# mini-v1_6-spacing.net
KiCad netlist of a schematic drawn in EAGLE
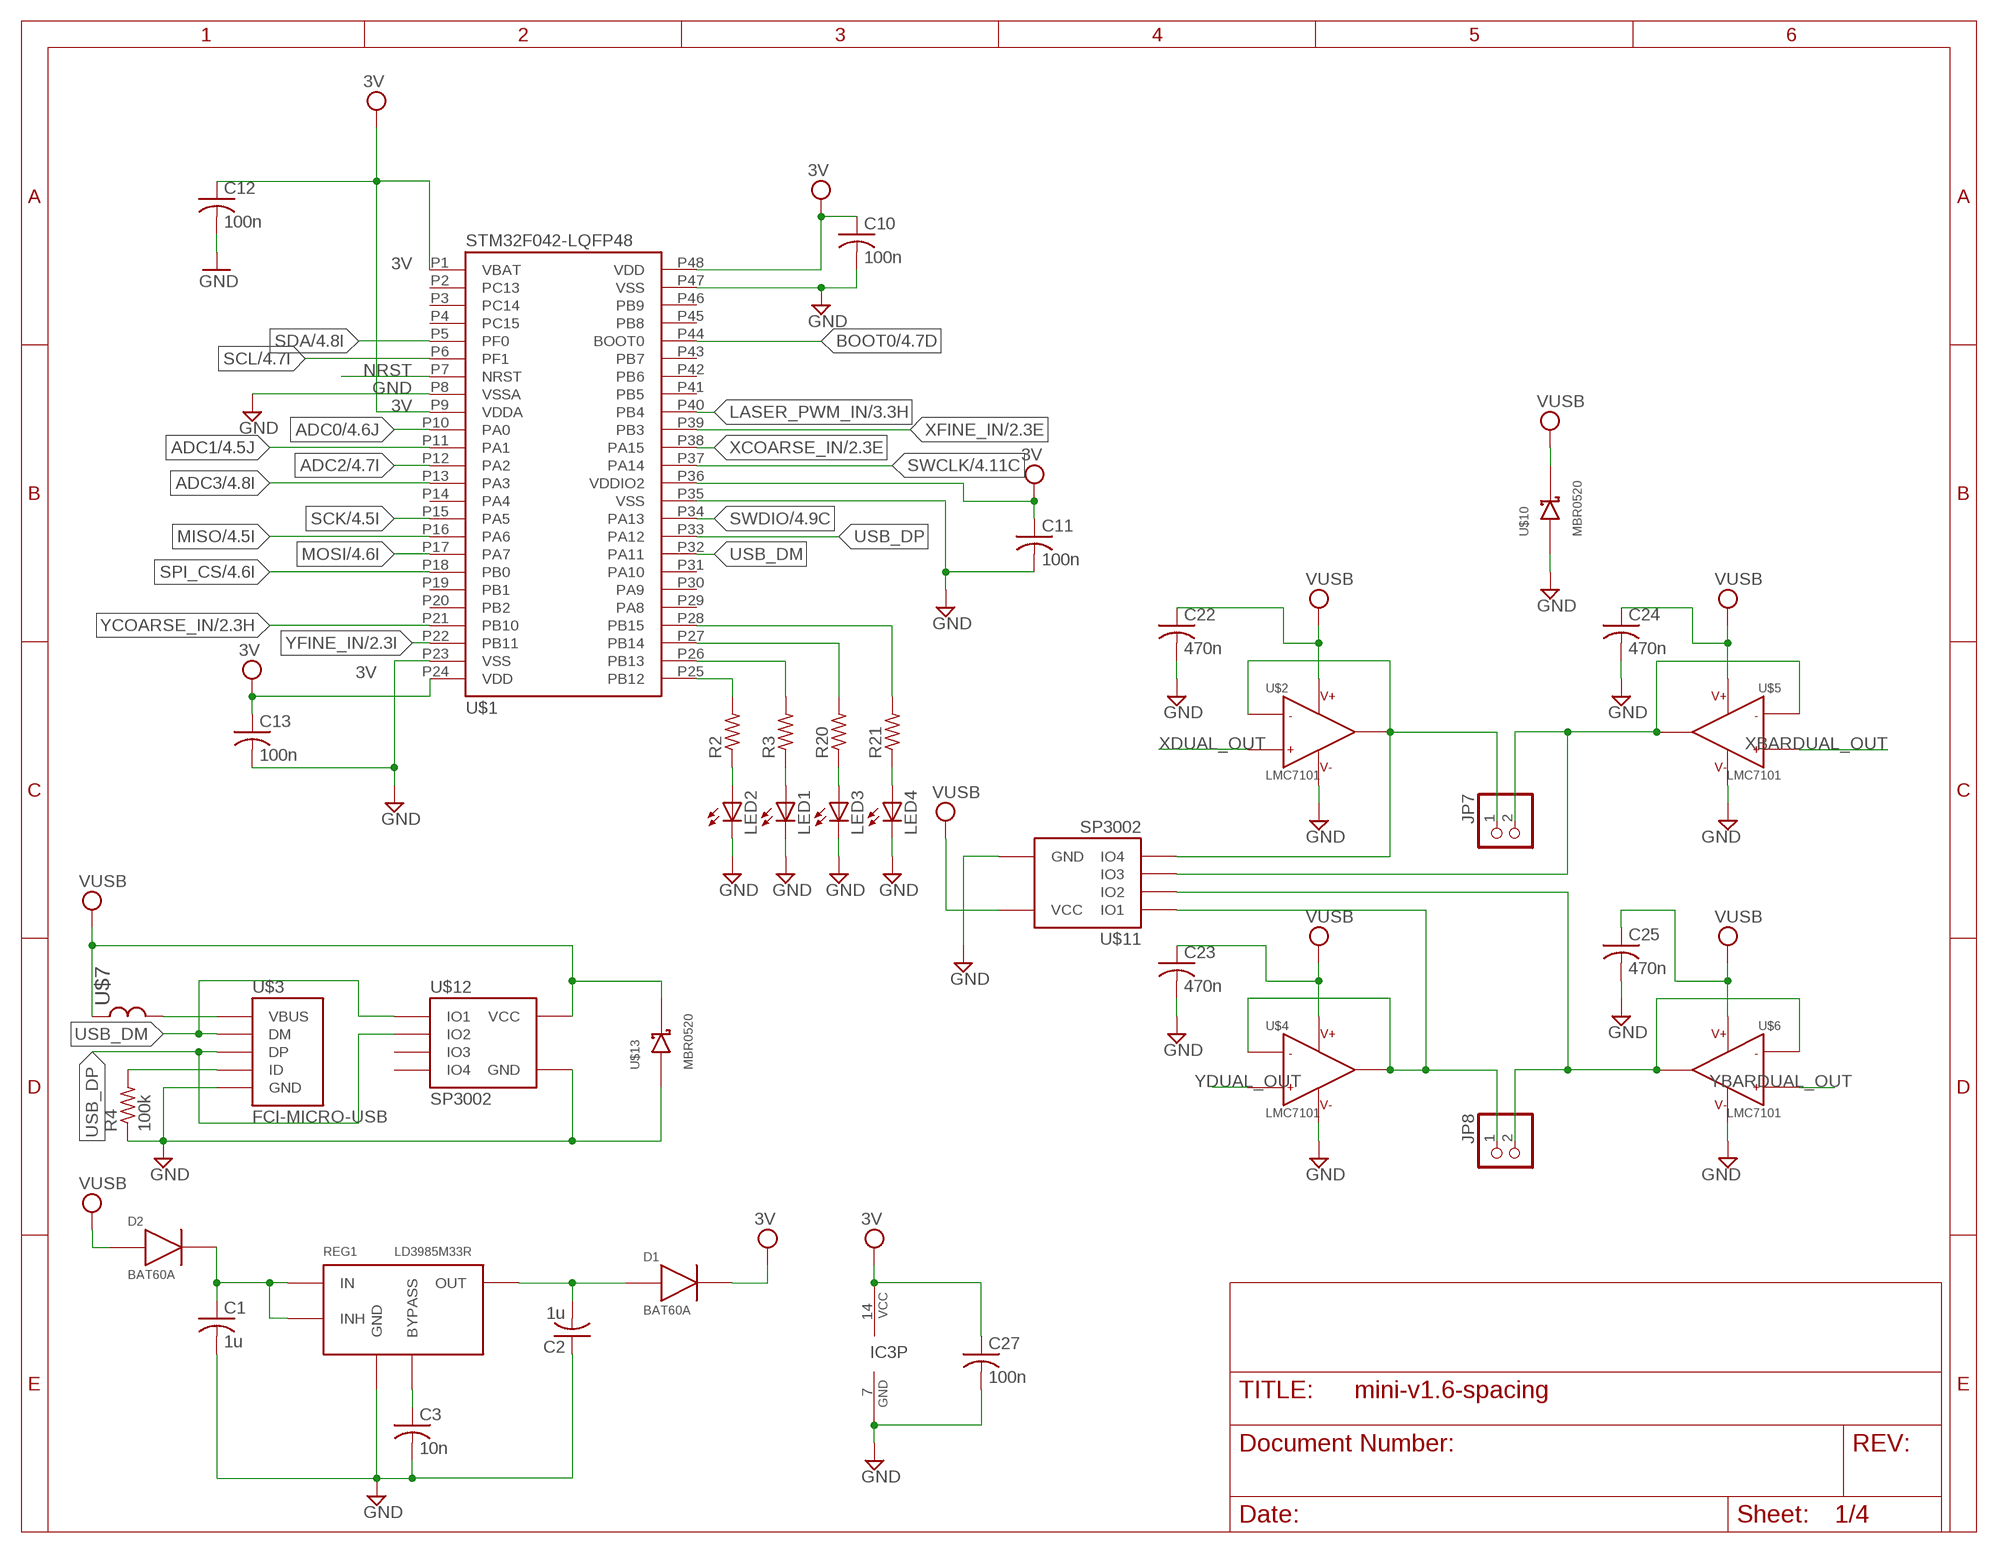
[diagram p0: schematic, sheet 1]
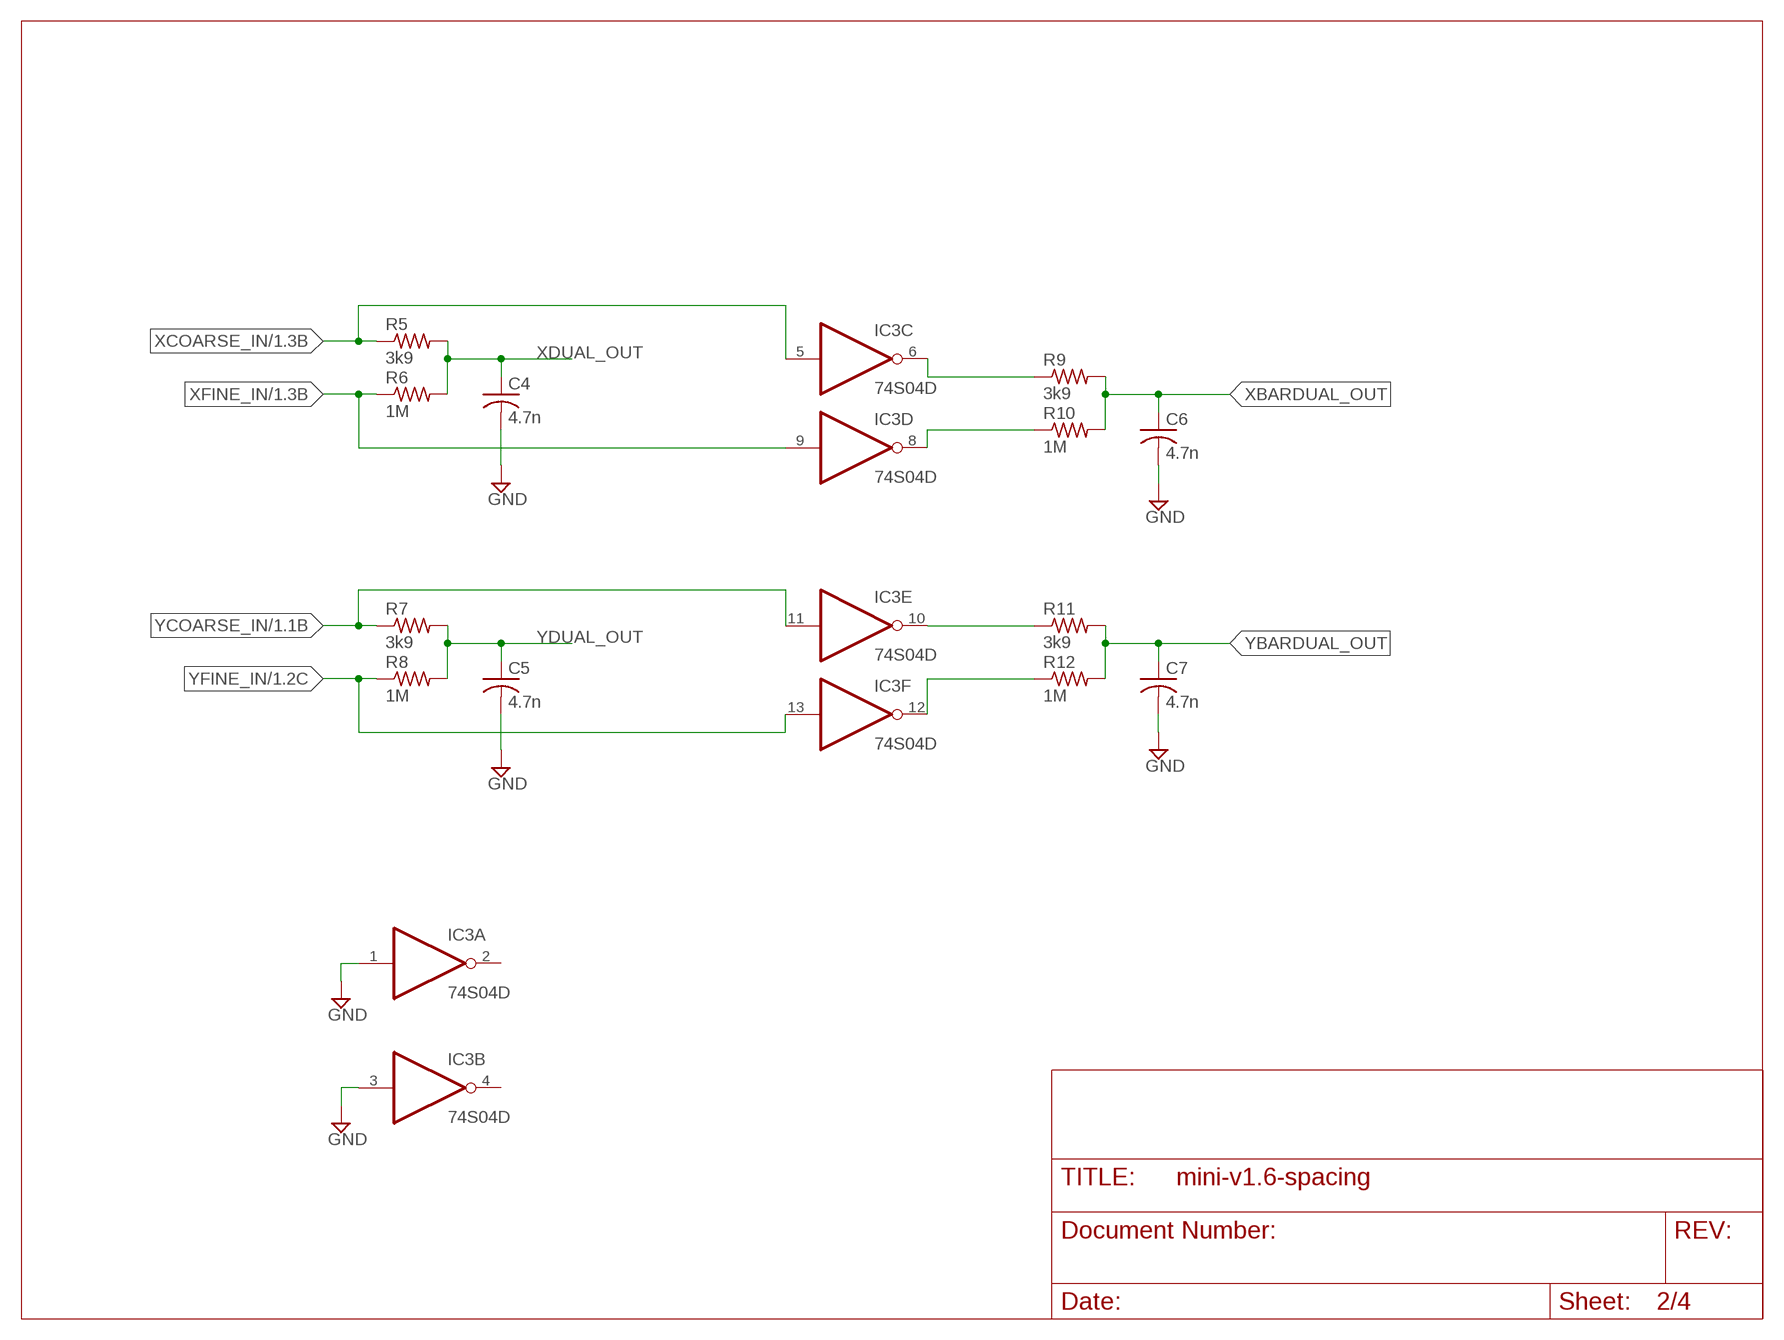
[diagram p1: schematic, sheet 2]
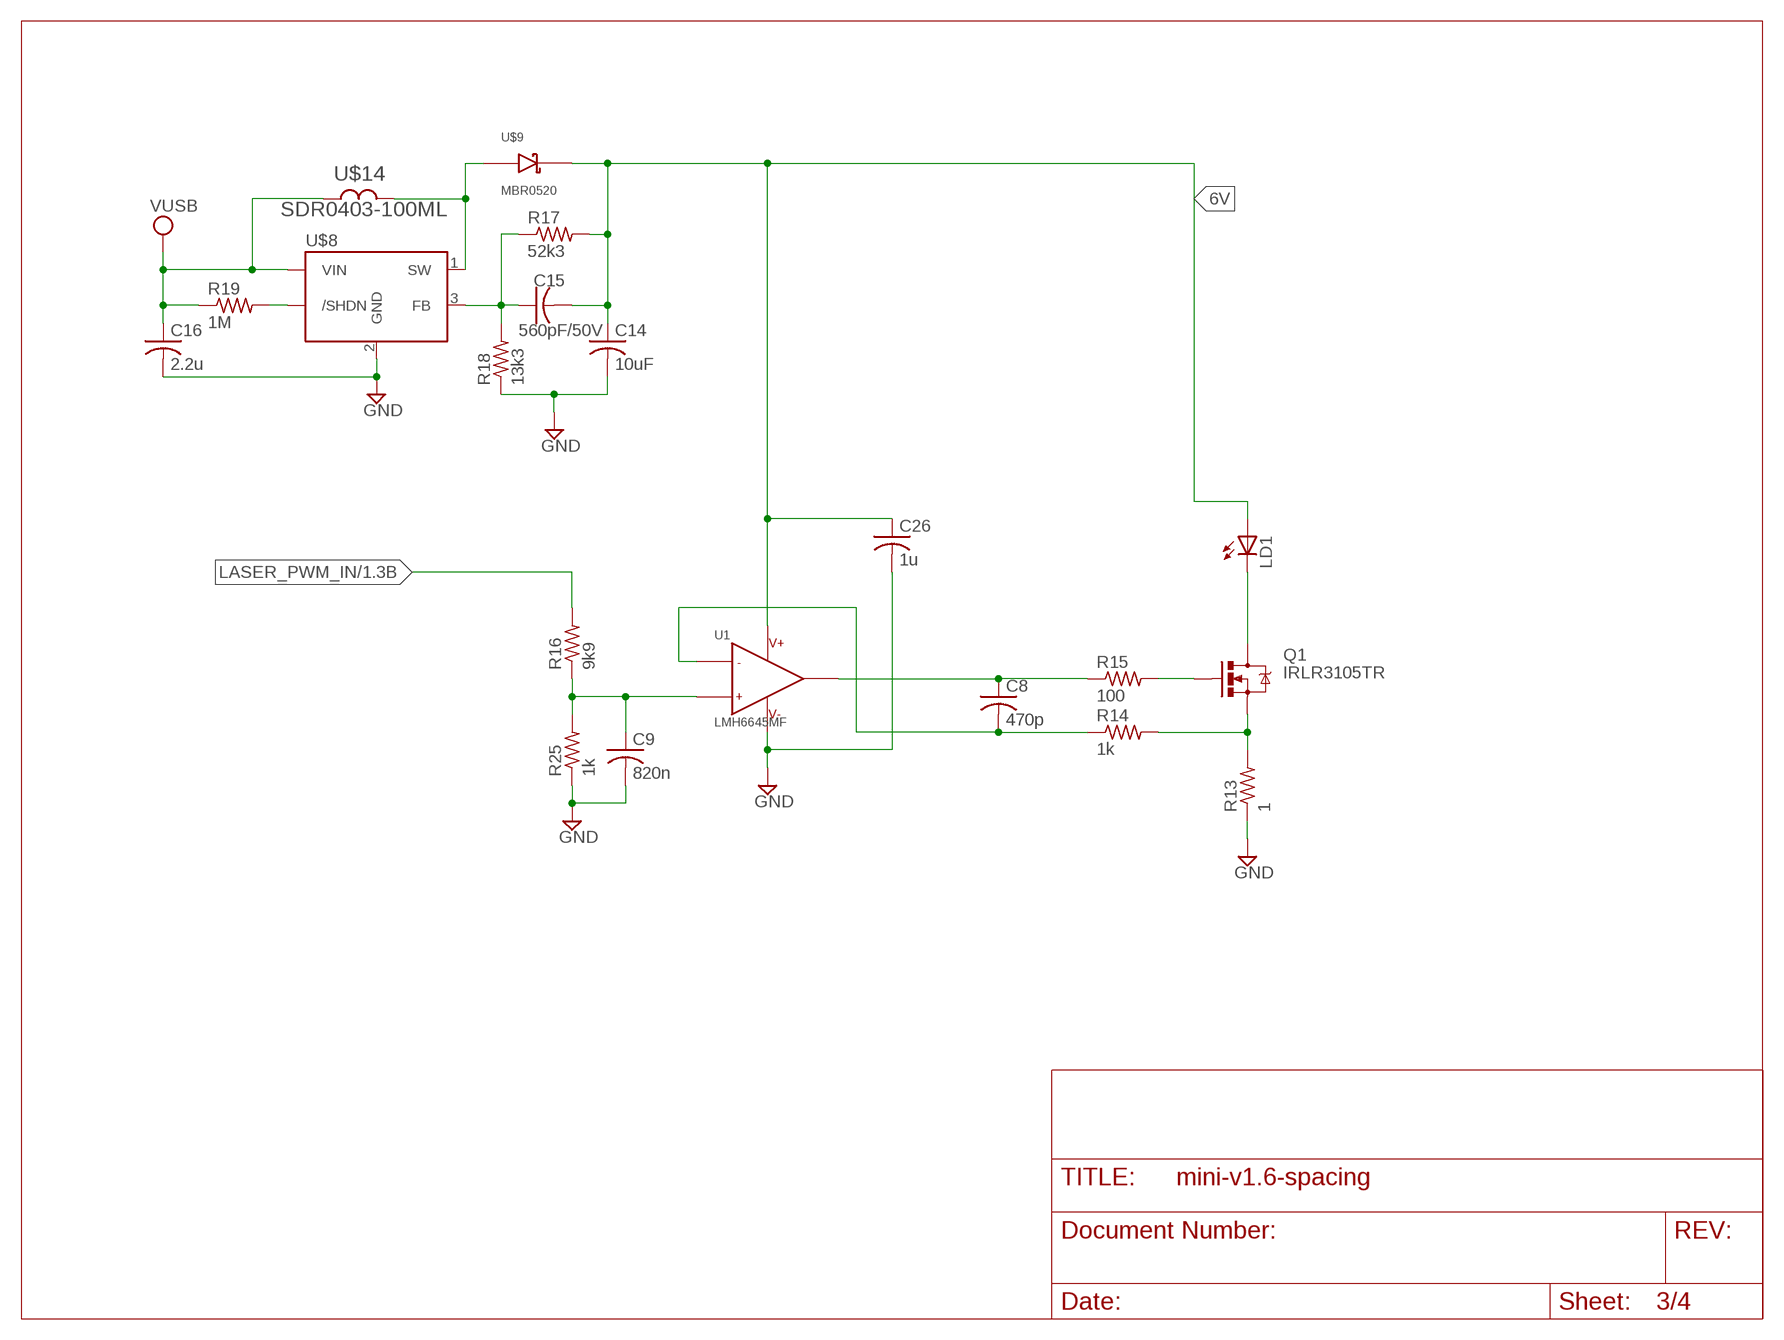
[diagram p2: schematic, sheet 3]
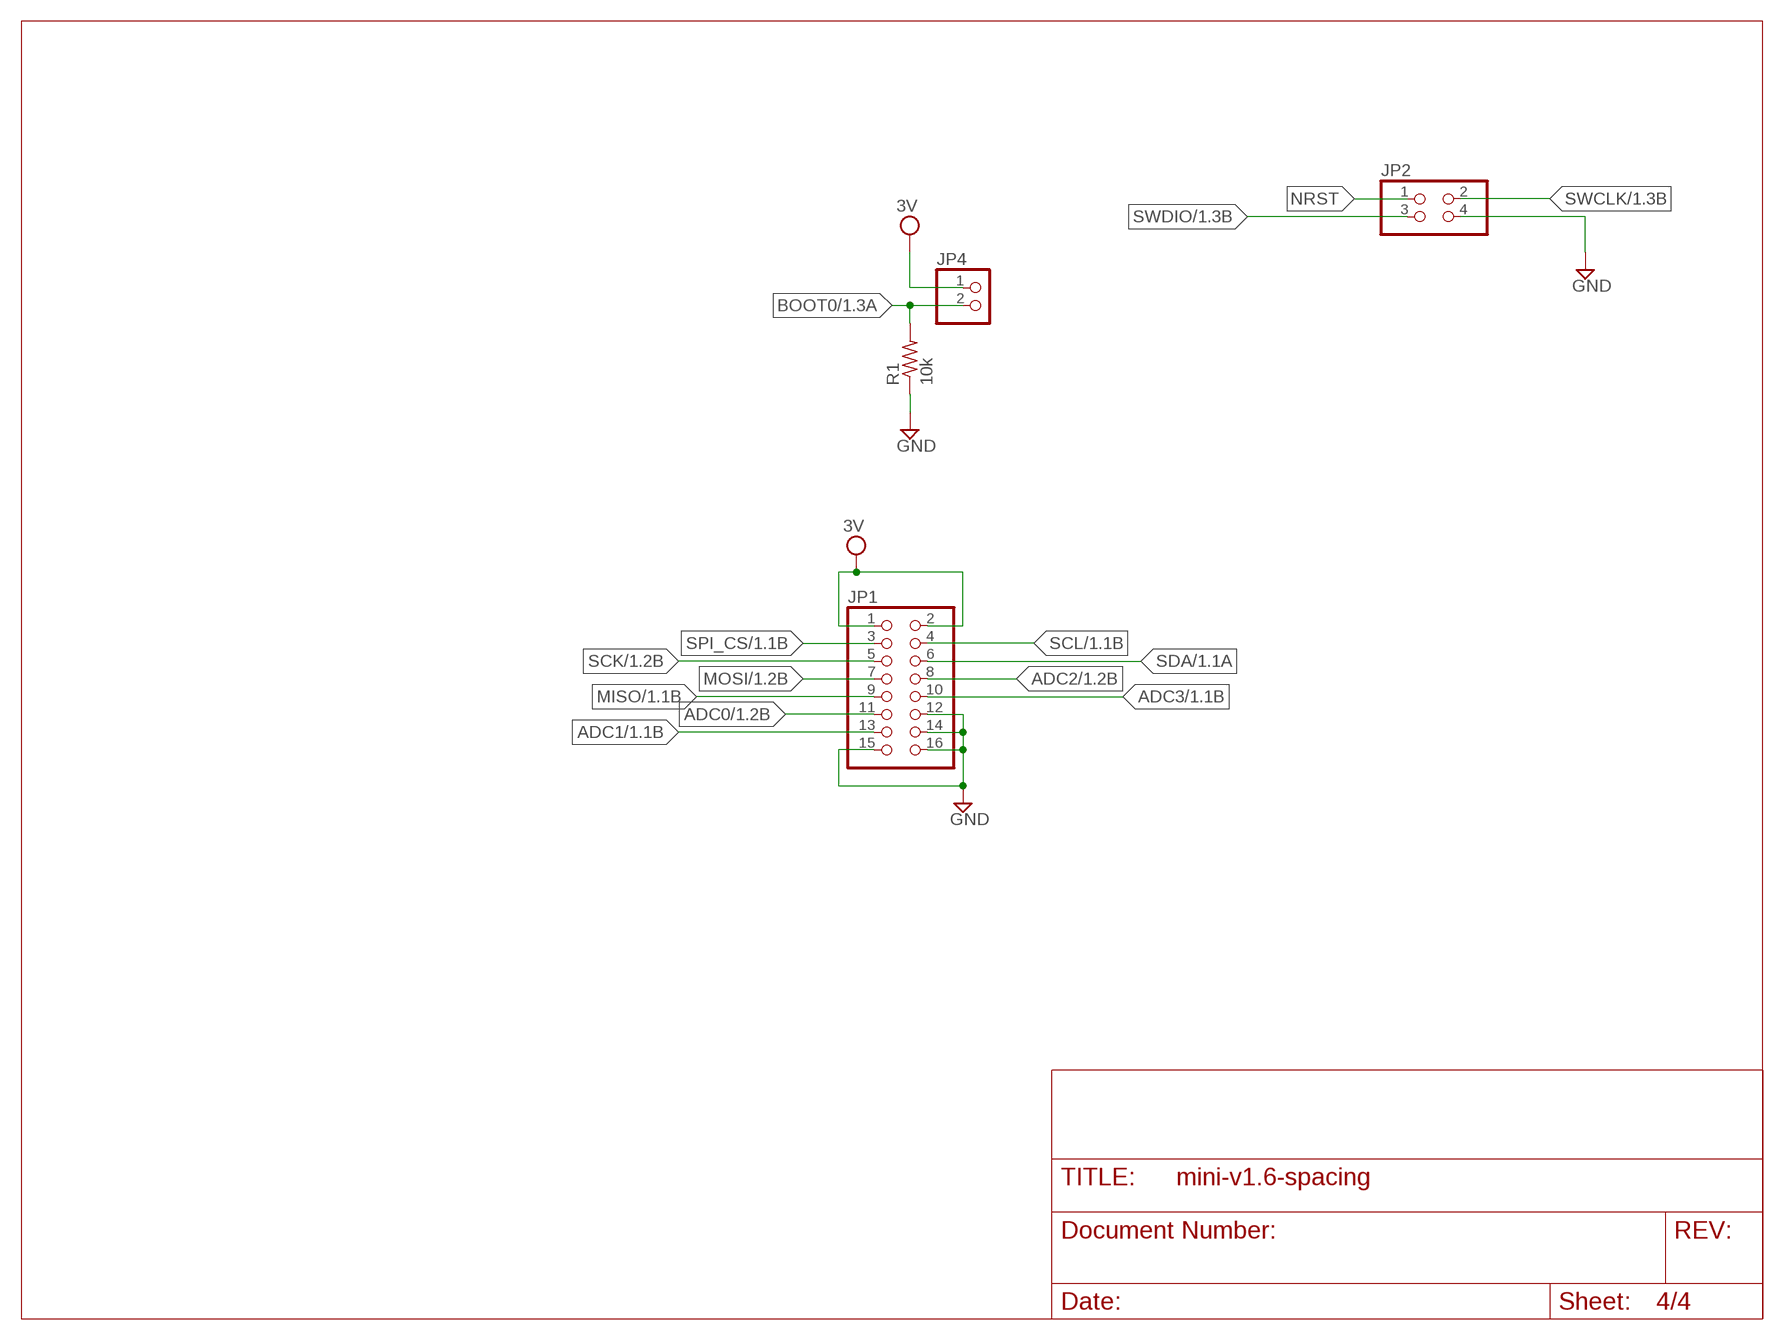
[diagram p3: schematic, sheet 4]

(export (version "E")
  (design (tool "Eeschema 10.0.6"))
  (components
    (comp (ref "C1")
      (value "1u")
      (footprint "eagle-import:C0603")
      (libsource (lib "eagle-import") (part "C-USC0603"))
    )
    (comp (ref "C2")
      (value "1u")
      (footprint "eagle-import:C0603")
      (libsource (lib "eagle-import") (part "C-USC0603"))
    )
    (comp (ref "C3")
      (value "10n")
      (footprint "eagle-import:C0603")
      (libsource (lib "eagle-import") (part "C-USC0603"))
    )
    (comp (ref "C10")
      (value "100n")
      (footprint "eagle-import:C0603")
      (libsource (lib "eagle-import") (part "C-USC0603"))
    )
    (comp (ref "C11")
      (value "100n")
      (footprint "eagle-import:C0603")
      (libsource (lib "eagle-import") (part "C-USC0603"))
    )
    (comp (ref "C12")
      (value "100n")
      (footprint "eagle-import:C0603")
      (libsource (lib "eagle-import") (part "C-USC0603"))
    )
    (comp (ref "C13")
      (value "100n")
      (footprint "eagle-import:C0603")
      (libsource (lib "eagle-import") (part "C-USC0603"))
    )
    (comp (ref "C22")
      (value "470n")
      (footprint "eagle-import:C0603")
      (libsource (lib "eagle-import") (part "C-USC0603"))
    )
    (comp (ref "C23")
      (value "470n")
      (footprint "eagle-import:C0603")
      (libsource (lib "eagle-import") (part "C-USC0603"))
    )
    (comp (ref "C24")
      (value "470n")
      (footprint "eagle-import:C0603")
      (libsource (lib "eagle-import") (part "C-USC0603"))
    )
    (comp (ref "C25")
      (value "470n")
      (footprint "eagle-import:C0603")
      (libsource (lib "eagle-import") (part "C-USC0603"))
    )
    (comp (ref "C27")
      (value "100n")
      (footprint "eagle-import:C0603")
      (libsource (lib "eagle-import") (part "C-USC0603"))
    )
    (comp (ref "D1")
      (value "BAT60A")
      (footprint "eagle-import:SOD323")
      (libsource (lib "eagle-import") (part "BAT60A"))
    )
    (comp (ref "D2")
      (value "BAT60A")
      (footprint "eagle-import:SOD323")
      (libsource (lib "eagle-import") (part "BAT60A"))
    )
    (comp (ref "IC3")
      (value "74S04D")
      (footprint "eagle-import:SO14")
      (libsource (lib "eagle-import") (part "7404DS"))
    )
    (comp (ref "JP7")
      (value "PINHD-1X2")
      (footprint "eagle-import:1X02")
      (libsource (lib "eagle-import") (part "PINHD-1X2"))
    )
    (comp (ref "JP8")
      (value "PINHD-1X2")
      (footprint "eagle-import:1X02")
      (libsource (lib "eagle-import") (part "PINHD-1X2"))
    )
    (comp (ref "LED1")
      (value "LEDCHIP-LED0603")
      (footprint "eagle-import:CHIP-LED0603")
      (libsource (lib "eagle-import") (part "LEDCHIP-LED0603"))
    )
    (comp (ref "LED2")
      (value "LEDCHIP-LED0603")
      (footprint "eagle-import:CHIP-LED0603")
      (libsource (lib "eagle-import") (part "LEDCHIP-LED0603"))
    )
    (comp (ref "LED3")
      (value "LEDCHIP-LED0603")
      (footprint "eagle-import:CHIP-LED0603")
      (libsource (lib "eagle-import") (part "LEDCHIP-LED0603"))
    )
    (comp (ref "LED4")
      (value "LEDCHIP-LED0603")
      (footprint "eagle-import:CHIP-LED0603")
      (libsource (lib "eagle-import") (part "LEDCHIP-LED0603"))
    )
    (comp (ref "R2")
      (value "R-US_R0603")
      (footprint "eagle-import:R0603")
      (libsource (lib "eagle-import") (part "R-US_R0603"))
    )
    (comp (ref "R3")
      (value "R-US_R0603")
      (footprint "eagle-import:R0603")
      (libsource (lib "eagle-import") (part "R-US_R0603"))
    )
    (comp (ref "R4")
      (value "100k")
      (footprint "eagle-import:R0603")
      (libsource (lib "eagle-import") (part "R-US_R0603"))
    )
    (comp (ref "R20")
      (value "R-US_R0603")
      (footprint "eagle-import:R0603")
      (libsource (lib "eagle-import") (part "R-US_R0603"))
    )
    (comp (ref "R21")
      (value "R-US_R0603")
      (footprint "eagle-import:R0603")
      (libsource (lib "eagle-import") (part "R-US_R0603"))
    )
    (comp (ref "REG1")
      (value "LD3985M33R")
      (footprint "eagle-import:SOT23-5L")
      (libsource (lib "eagle-import") (part "LD3985MXXR"))
    )
    (comp (ref "U$1")
      (value "STM32F042-LQFP48")
      (footprint "eagle-import:LQFP48")
      (libsource (lib "eagle-import") (part "STM32F042-LQFP48"))
    )
    (comp (ref "U$2")
      (value "LMC7101")
      (footprint "eagle-import:SOT23-5")
      (libsource (lib "eagle-import") (part "LMC7101"))
    )
    (comp (ref "U$3")
      (value "FCI-MICRO-USB")
      (footprint "eagle-import:FCI-MICROUSB")
      (libsource (lib "eagle-import") (part "FCI-MICRO-USB"))
    )
    (comp (ref "U$4")
      (value "LMC7101")
      (footprint "eagle-import:SOT23-5")
      (libsource (lib "eagle-import") (part "LMC7101"))
    )
    (comp (ref "U$5")
      (value "LMC7101")
      (footprint "eagle-import:SOT23-5")
      (libsource (lib "eagle-import") (part "LMC7101"))
    )
    (comp (ref "U$6")
      (value "LMC7101")
      (footprint "eagle-import:SOT23-5")
      (libsource (lib "eagle-import") (part "LMC7101"))
    )
    (comp (ref "U$7")
      (value "L_TDK_1005")
      (footprint "eagle-import:MLK1005")
      (libsource (lib "eagle-import") (part "L_TDK_1005"))
    )
    (comp (ref "U$10")
      (value "MBR0520")
      (footprint "eagle-import:SOD123")
      (libsource (lib "eagle-import") (part "MBR0520"))
    )
    (comp (ref "U$11")
      (value "SP3002")
      (footprint "eagle-import:SC70-6")
      (libsource (lib "eagle-import") (part "SP3002"))
    )
    (comp (ref "U$12")
      (value "SP3002")
      (footprint "eagle-import:SC70-6")
      (libsource (lib "eagle-import") (part "SP3002"))
    )
    (comp (ref "U$13")
      (value "MBR0520")
      (footprint "eagle-import:SOD123")
      (libsource (lib "eagle-import") (part "MBR0520"))
    )
    (comp (ref "C4")
      (value "4.7n")
      (footprint "eagle-import:C0603")
      (libsource (lib "eagle-import") (part "C-USC0603"))
    )
    (comp (ref "C5")
      (value "4.7n")
      (footprint "eagle-import:C0603")
      (libsource (lib "eagle-import") (part "C-USC0603"))
    )
    (comp (ref "C6")
      (value "4.7n")
      (footprint "eagle-import:C0603")
      (libsource (lib "eagle-import") (part "C-USC0603"))
    )
    (comp (ref "C7")
      (value "4.7n")
      (footprint "eagle-import:C0603")
      (libsource (lib "eagle-import") (part "C-USC0603"))
    )
    (comp (ref "R5")
      (value "3k9")
      (footprint "eagle-import:R0603")
      (libsource (lib "eagle-import") (part "R-US_R0603"))
    )
    (comp (ref "R6")
      (value "1M")
      (footprint "eagle-import:R0603")
      (libsource (lib "eagle-import") (part "R-US_R0603"))
    )
    (comp (ref "R7")
      (value "3k9")
      (footprint "eagle-import:R0603")
      (libsource (lib "eagle-import") (part "R-US_R0603"))
    )
    (comp (ref "R8")
      (value "1M")
      (footprint "eagle-import:R0603")
      (libsource (lib "eagle-import") (part "R-US_R0603"))
    )
    (comp (ref "R9")
      (value "3k9")
      (footprint "eagle-import:R0603")
      (libsource (lib "eagle-import") (part "R-US_R0603"))
    )
    (comp (ref "R10")
      (value "1M")
      (footprint "eagle-import:R0603")
      (libsource (lib "eagle-import") (part "R-US_R0603"))
    )
    (comp (ref "R11")
      (value "3k9")
      (footprint "eagle-import:R0603")
      (libsource (lib "eagle-import") (part "R-US_R0603"))
    )
    (comp (ref "R12")
      (value "1M")
      (footprint "eagle-import:R0603")
      (libsource (lib "eagle-import") (part "R-US_R0603"))
    )
    (comp (ref "C8")
      (value "470p")
      (footprint "eagle-import:C0603")
      (libsource (lib "eagle-import") (part "C-USC0603"))
    )
    (comp (ref "C9")
      (value "820n")
      (footprint "eagle-import:C0603")
      (libsource (lib "eagle-import") (part "C-USC0603"))
    )
    (comp (ref "C14")
      (value "10uF")
      (footprint "eagle-import:C0603")
      (libsource (lib "eagle-import") (part "C-USC0603"))
    )
    (comp (ref "C15")
      (value "560pF/50V")
      (footprint "eagle-import:C0603")
      (libsource (lib "eagle-import") (part "C-USC0603"))
    )
    (comp (ref "C16")
      (value "2.2u")
      (footprint "eagle-import:C0603")
      (libsource (lib "eagle-import") (part "C-USC0603"))
    )
    (comp (ref "C26")
      (value "1u")
      (footprint "eagle-import:C0603")
      (libsource (lib "eagle-import") (part "C-USC0603"))
    )
    (comp (ref "LD1")
      (value "LASERDIODELD2")
      (footprint "eagle-import:LASERDIODE2")
      (fields (field (name "MPN") "3 x (0552-2-15-15-11-27-10-0)"))
      (libsource (lib "eagle-import") (part "LASERDIODELD2"))
    )
    (comp (ref "Q1")
      (value "IRLR3105TR")
      (footprint "eagle-import:DPAK")
      (libsource (lib "eagle-import") (part "FET-N-IRLR3105TRIRLR3105TR"))
    )
    (comp (ref "R13")
      (value "1")
      (footprint "eagle-import:R0603")
      (libsource (lib "eagle-import") (part "R-US_R0603"))
    )
    (comp (ref "R14")
      (value "1k")
      (footprint "eagle-import:R0603")
      (libsource (lib "eagle-import") (part "R-US_R0603"))
    )
    (comp (ref "R15")
      (value "100")
      (footprint "eagle-import:R0603")
      (libsource (lib "eagle-import") (part "R-US_R0603"))
    )
    (comp (ref "R16")
      (value "9k9")
      (footprint "eagle-import:R0603")
      (libsource (lib "eagle-import") (part "R-US_R0603"))
    )
    (comp (ref "R17")
      (value "52k3")
      (footprint "eagle-import:R0603")
      (libsource (lib "eagle-import") (part "R-US_R0603"))
    )
    (comp (ref "R18")
      (value "13k3")
      (footprint "eagle-import:R0603")
      (libsource (lib "eagle-import") (part "R-US_R0603"))
    )
    (comp (ref "R19")
      (value "1M")
      (footprint "eagle-import:R0603")
      (libsource (lib "eagle-import") (part "R-US_R0603"))
    )
    (comp (ref "R25")
      (value "1k")
      (footprint "eagle-import:R0603")
      (libsource (lib "eagle-import") (part "R-US_R0603"))
    )
    (comp (ref "U$8")
      (value "LMR62014")
      (footprint "eagle-import:SOT23-5")
      (libsource (lib "eagle-import") (part "LMR62014"))
    )
    (comp (ref "U$9")
      (value "MBR0520")
      (footprint "eagle-import:SOD123")
      (libsource (lib "eagle-import") (part "MBR0520"))
    )
    (comp (ref "U$14")
      (value "SDR0403-100ML")
      (footprint "eagle-import:SDR0403")
      (libsource (lib "eagle-import") (part "SDR0403"))
    )
    (comp (ref "U1")
      (value "LMH6645MF")
      (footprint "eagle-import:SOT23-5")
      (libsource (lib "eagle-import") (part "OPAMP-SINGLELMH6645MF"))
    )
    (comp (ref "JP1")
      (value "PINHD-2X8")
      (footprint "eagle-import:2X08")
      (libsource (lib "eagle-import") (part "PINHD-2X8"))
    )
    (comp (ref "JP2")
      (value "PINHD-2X2")
      (footprint "eagle-import:2X02")
      (libsource (lib "eagle-import") (part "PINHD-2X2"))
    )
    (comp (ref "JP4")
      (value "PINHD-1X2")
      (footprint "eagle-import:1X02")
      (libsource (lib "eagle-import") (part "PINHD-1X2"))
    )
    (comp (ref "R1")
      (value "10k")
      (footprint "eagle-import:R0603")
      (libsource (lib "eagle-import") (part "R-US_R0603"))
    )
  )
  (nets
    (net (code "1") (name "3V") (class "Default")
      (node (ref "C10") (pin "1") (pinfunction "1_1") (pintype "passive"))
      (node (ref "C11") (pin "1") (pinfunction "1_1") (pintype "passive"))
      (node (ref "C12") (pin "1") (pinfunction "1_1") (pintype "passive"))
      (node (ref "C13") (pin "1") (pinfunction "1_1") (pintype "passive"))
      (node (ref "C27") (pin "1") (pinfunction "1_1") (pintype "passive"))
      (node (ref "D1") (pin "1") (pinfunction "1_1") (pintype "bidirectional"))
      (node (ref "IC3") (pin "14") (pinfunction "VCC_14") (pintype "power_in"))
      (node (ref "JP1") (pin "1") (pinfunction "1_1") (pintype "passive"))
      (node (ref "JP1") (pin "2") (pinfunction "2_2") (pintype "passive"))
      (node (ref "JP4") (pin "1") (pinfunction "1_1") (pintype "passive"))
      (node (ref "U$1") (pin "P1") (pinfunction "VBAT_P1") (pintype "bidirectional"))
      (node (ref "U$1") (pin "P24") (pinfunction "VDD_P24") (pintype "bidirectional"))
      (node (ref "U$1") (pin "P36") (pinfunction "VDDIO2_P36") (pintype "bidirectional"))
      (node (ref "U$1") (pin "P48") (pinfunction "VDD_P48") (pintype "bidirectional"))
      (node (ref "U$1") (pin "P9") (pinfunction "VDDA_P9") (pintype "bidirectional"))
    )
    (net (code "2") (name "6V") (class "Default")
      (node (ref "C14") (pin "1") (pinfunction "1_1") (pintype "passive"))
      (node (ref "C15") (pin "2") (pinfunction "2_2") (pintype "passive"))
      (node (ref "C26") (pin "1") (pinfunction "1_1") (pintype "passive"))
      (node (ref "LD1") (pin "P$1") (pinfunction "A_P$1") (pintype "passive"))
      (node (ref "R17") (pin "2") (pinfunction "2_2") (pintype "passive"))
      (node (ref "U$9") (pin "CATHODE") (pinfunction "CATHODE_CATHODE") (pintype "bidirectional"))
      (node (ref "U1") (pin "5") (pinfunction "V+_5") (pintype "power_in"))
    )
    (net (code "3") (name "ADC0") (class "Default")
      (node (ref "JP1") (pin "11") (pinfunction "11_11") (pintype "passive"))
      (node (ref "U$1") (pin "P10") (pinfunction "PA0_P10") (pintype "bidirectional"))
    )
    (net (code "4") (name "ADC1") (class "Default")
      (node (ref "JP1") (pin "13") (pinfunction "13_13") (pintype "passive"))
      (node (ref "U$1") (pin "P11") (pinfunction "PA1_P11") (pintype "bidirectional"))
    )
    (net (code "5") (name "ADC2") (class "Default")
      (node (ref "JP1") (pin "8") (pinfunction "8_8") (pintype "passive"))
      (node (ref "U$1") (pin "P12") (pinfunction "PA2_P12") (pintype "bidirectional"))
    )
    (net (code "6") (name "ADC3") (class "Default")
      (node (ref "JP1") (pin "10") (pinfunction "10_10") (pintype "passive"))
      (node (ref "U$1") (pin "P13") (pinfunction "PA3_P13") (pintype "bidirectional"))
    )
    (net (code "7") (name "BOOT0") (class "Default")
      (node (ref "JP4") (pin "2") (pinfunction "2_2") (pintype "passive"))
      (node (ref "R1") (pin "2") (pinfunction "2_2") (pintype "passive"))
      (node (ref "U$1") (pin "P44") (pinfunction "BOOT0_P44") (pintype "bidirectional"))
    )
    (net (code "8") (name "GND") (class "Default")
      (node (ref "C1") (pin "2") (pinfunction "2_2") (pintype "passive"))
      (node (ref "C10") (pin "2") (pinfunction "2_2") (pintype "passive"))
      (node (ref "C11") (pin "2") (pinfunction "2_2") (pintype "passive"))
      (node (ref "C12") (pin "2") (pinfunction "2_2") (pintype "passive"))
      (node (ref "C13") (pin "2") (pinfunction "2_2") (pintype "passive"))
      (node (ref "C14") (pin "2") (pinfunction "2_2") (pintype "passive"))
      (node (ref "C16") (pin "2") (pinfunction "2_2") (pintype "passive"))
      (node (ref "C2") (pin "1") (pinfunction "1_1") (pintype "passive"))
      (node (ref "C22") (pin "2") (pinfunction "2_2") (pintype "passive"))
      (node (ref "C23") (pin "2") (pinfunction "2_2") (pintype "passive"))
      (node (ref "C24") (pin "2") (pinfunction "2_2") (pintype "passive"))
      (node (ref "C25") (pin "2") (pinfunction "2_2") (pintype "passive"))
      (node (ref "C26") (pin "2") (pinfunction "2_2") (pintype "passive"))
      (node (ref "C27") (pin "2") (pinfunction "2_2") (pintype "passive"))
      (node (ref "C3") (pin "2") (pinfunction "2_2") (pintype "passive"))
      (node (ref "C4") (pin "2") (pinfunction "2_2") (pintype "passive"))
      (node (ref "C5") (pin "2") (pinfunction "2_2") (pintype "passive"))
      (node (ref "C6") (pin "2") (pinfunction "2_2") (pintype "passive"))
      (node (ref "C7") (pin "2") (pinfunction "2_2") (pintype "passive"))
      (node (ref "C9") (pin "2") (pinfunction "2_2") (pintype "passive"))
      (node (ref "IC3") (pin "1") (pinfunction "I_1") (pintype "input"))
      (node (ref "IC3") (pin "3") (pinfunction "I_3") (pintype "input"))
      (node (ref "IC3") (pin "7") (pinfunction "GND_7") (pintype "power_in"))
      (node (ref "JP1") (pin "12") (pinfunction "12_12") (pintype "passive"))
      (node (ref "JP1") (pin "14") (pinfunction "14_14") (pintype "passive"))
      (node (ref "JP1") (pin "15") (pinfunction "15_15") (pintype "passive"))
      (node (ref "JP1") (pin "16") (pinfunction "16_16") (pintype "passive"))
      (node (ref "JP2") (pin "4") (pinfunction "4_4") (pintype "passive"))
      (node (ref "LED1") (pin "C") (pinfunction "C_C") (pintype "passive"))
      (node (ref "LED2") (pin "C") (pinfunction "C_C") (pintype "passive"))
      (node (ref "LED3") (pin "C") (pinfunction "C_C") (pintype "passive"))
      (node (ref "LED4") (pin "C") (pinfunction "C_C") (pintype "passive"))
      (node (ref "R1") (pin "1") (pinfunction "1_1") (pintype "passive"))
      (node (ref "R13") (pin "1") (pinfunction "1_1") (pintype "passive"))
      (node (ref "R18") (pin "1") (pinfunction "1_1") (pintype "passive"))
      (node (ref "R25") (pin "1") (pinfunction "1_1") (pintype "passive"))
      (node (ref "R4") (pin "1") (pinfunction "1_1") (pintype "passive"))
      (node (ref "REG1") (pin "GND") (pinfunction "GND_GND") (pintype "bidirectional"))
      (node (ref "U$1") (pin "P23") (pinfunction "VSS_P23") (pintype "bidirectional"))
      (node (ref "U$1") (pin "P35") (pinfunction "VSS_P35") (pintype "bidirectional"))
      (node (ref "U$1") (pin "P47") (pinfunction "VSS_P47") (pintype "bidirectional"))
      (node (ref "U$1") (pin "P8") (pinfunction "VSSA_P8") (pintype "bidirectional"))
      (node (ref "U$10") (pin "ANODE") (pinfunction "ANODE_ANODE") (pintype "bidirectional"))
      (node (ref "U$11") (pin "P2") (pinfunction "GND_P2") (pintype "power_in"))
      (node (ref "U$12") (pin "P2") (pinfunction "GND_P2") (pintype "power_in"))
      (node (ref "U$13") (pin "ANODE") (pinfunction "ANODE_ANODE") (pintype "bidirectional"))
      (node (ref "U$2") (pin "5") (pinfunction "P5_5") (pintype "power_in"))
      (node (ref "U$3") (pin "P5") (pinfunction "GND_P5") (pintype "bidirectional"))
      (node (ref "U$4") (pin "5") (pinfunction "P5_5") (pintype "power_in"))
      (node (ref "U$5") (pin "5") (pinfunction "P5_5") (pintype "power_in"))
      (node (ref "U$6") (pin "5") (pinfunction "P5_5") (pintype "power_in"))
      (node (ref "U$8") (pin "2") (pinfunction "GND_2") (pintype "bidirectional"))
      (node (ref "U1") (pin "2") (pinfunction "V-_2") (pintype "power_in"))
    )
    (net (code "9") (name "LASER_PWM_IN") (class "Default")
      (node (ref "R16") (pin "2") (pinfunction "2_2") (pintype "passive"))
      (node (ref "U$1") (pin "P40") (pinfunction "PB4_P40") (pintype "bidirectional"))
    )
    (net (code "10") (name "MISO") (class "Default")
      (node (ref "JP1") (pin "9") (pinfunction "9_9") (pintype "passive"))
      (node (ref "U$1") (pin "P16") (pinfunction "PA6_P16") (pintype "bidirectional"))
    )
    (net (code "11") (name "MOSI") (class "Default")
      (node (ref "JP1") (pin "7") (pinfunction "7_7") (pintype "passive"))
      (node (ref "U$1") (pin "P17") (pinfunction "PA7_P17") (pintype "bidirectional"))
    )
    (net (code "12") (name "NRST") (class "Default")
      (node (ref "JP2") (pin "1") (pinfunction "1_1") (pintype "passive"))
      (node (ref "U$1") (pin "P7") (pinfunction "NRST_P7") (pintype "bidirectional"))
    )
    (net (code "13") (name "Net-(C2-Pad2)") (class "Default")
      (node (ref "C2") (pin "2") (pinfunction "2_2") (pintype "passive"))
      (node (ref "D1") (pin "2") (pinfunction "2_2") (pintype "bidirectional"))
      (node (ref "REG1") (pin "OUT") (pinfunction "OUT_OUT") (pintype "bidirectional"))
    )
    (net (code "14") (name "Net-(C3-Pad1)") (class "Default")
      (node (ref "C3") (pin "1") (pinfunction "1_1") (pintype "passive"))
      (node (ref "REG1") (pin "BYPASS") (pinfunction "BYPASS_BYPASS") (pintype "bidirectional"))
    )
    (net (code "15") (name "Net-(IC3C-O)") (class "Default")
      (node (ref "IC3") (pin "6") (pinfunction "O_6") (pintype "output"))
      (node (ref "R9") (pin "1") (pinfunction "1_1") (pintype "passive"))
    )
    (net (code "16") (name "Net-(IC3D-O)") (class "Default")
      (node (ref "IC3") (pin "8") (pinfunction "O_8") (pintype "output"))
      (node (ref "R10") (pin "1") (pinfunction "1_1") (pintype "passive"))
    )
    (net (code "17") (name "Net-(IC3E-O)") (class "Default")
      (node (ref "IC3") (pin "10") (pinfunction "O_10") (pintype "output"))
      (node (ref "R11") (pin "1") (pinfunction "1_1") (pintype "passive"))
    )
    (net (code "18") (name "Net-(IC3F-O)") (class "Default")
      (node (ref "IC3") (pin "12") (pinfunction "O_12") (pintype "output"))
      (node (ref "R12") (pin "1") (pinfunction "1_1") (pintype "passive"))
    )
    (net (code "19") (name "Net-(LD1-C)") (class "Default")
      (node (ref "LD1") (pin "P$3") (pinfunction "C_P$3") (pintype "passive"))
      (node (ref "Q1") (pin "4") (pinfunction "D_4") (pintype "passive"))
    )
    (net (code "20") (name "Net-(LED1-PadA)") (class "Default")
      (node (ref "LED1") (pin "A") (pinfunction "A_A") (pintype "passive"))
      (node (ref "R3") (pin "1") (pinfunction "1_1") (pintype "passive"))
    )
    (net (code "21") (name "Net-(LED2-PadA)") (class "Default")
      (node (ref "LED2") (pin "A") (pinfunction "A_A") (pintype "passive"))
      (node (ref "R2") (pin "1") (pinfunction "1_1") (pintype "passive"))
    )
    (net (code "22") (name "Net-(LED3-PadA)") (class "Default")
      (node (ref "LED3") (pin "A") (pinfunction "A_A") (pintype "passive"))
      (node (ref "R20") (pin "1") (pinfunction "1_1") (pintype "passive"))
    )
    (net (code "23") (name "Net-(LED4-PadA)") (class "Default")
      (node (ref "LED4") (pin "A") (pinfunction "A_A") (pintype "passive"))
      (node (ref "R21") (pin "1") (pinfunction "1_1") (pintype "passive"))
    )
    (net (code "24") (name "Net-(Q1-G)") (class "Default")
      (node (ref "Q1") (pin "1") (pinfunction "G_1") (pintype "passive"))
      (node (ref "R15") (pin "2") (pinfunction "2_2") (pintype "passive"))
    )
    (net (code "25") (name "Net-(Q1-S)") (class "Default")
      (node (ref "Q1") (pin "3") (pinfunction "S_3") (pintype "passive"))
      (node (ref "R13") (pin "2") (pinfunction "2_2") (pintype "passive"))
      (node (ref "R14") (pin "2") (pinfunction "2_2") (pintype "passive"))
    )
    (net (code "26") (name "Net-(REG1-INH)") (class "Default")
      (node (ref "C1") (pin "1") (pinfunction "1_1") (pintype "passive"))
      (node (ref "D2") (pin "1") (pinfunction "1_1") (pintype "bidirectional"))
      (node (ref "REG1") (pin "IN") (pinfunction "IN_IN") (pintype "bidirectional"))
      (node (ref "REG1") (pin "INHIBIT") (pinfunction "INH_INHIBIT") (pintype "bidirectional"))
    )
    (net (code "27") (name "Net-(U$1-PB12)") (class "Default")
      (node (ref "R2") (pin "2") (pinfunction "2_2") (pintype "passive"))
      (node (ref "U$1") (pin "P25") (pinfunction "PB12_P25") (pintype "bidirectional"))
    )
    (net (code "28") (name "Net-(U$1-PB13)") (class "Default")
      (node (ref "R3") (pin "2") (pinfunction "2_2") (pintype "passive"))
      (node (ref "U$1") (pin "P26") (pinfunction "PB13_P26") (pintype "bidirectional"))
    )
    (net (code "29") (name "Net-(U$1-PB14)") (class "Default")
      (node (ref "R20") (pin "2") (pinfunction "2_2") (pintype "passive"))
      (node (ref "U$1") (pin "P27") (pinfunction "PB14_P27") (pintype "bidirectional"))
    )
    (net (code "30") (name "Net-(U$1-PB15)") (class "Default")
      (node (ref "R21") (pin "2") (pinfunction "2_2") (pintype "passive"))
      (node (ref "U$1") (pin "P28") (pinfunction "PB15_P28") (pintype "bidirectional"))
    )
    (net (code "31") (name "Net-(U$3-ID)") (class "Default")
      (node (ref "R4") (pin "2") (pinfunction "2_2") (pintype "passive"))
      (node (ref "U$3") (pin "P4") (pinfunction "ID_P4") (pintype "bidirectional"))
    )
    (net (code "32") (name "Net-(U$3-VBUS)") (class "Default")
      (node (ref "U$3") (pin "P1") (pinfunction "VBUS_P1") (pintype "bidirectional"))
      (node (ref "U$7") (pin "P$2") (pinfunction "P$2_P$2") (pintype "bidirectional"))
    )
    (net (code "33") (name "Net-(U$8-FB)") (class "Default")
      (node (ref "C15") (pin "1") (pinfunction "1_1") (pintype "passive"))
      (node (ref "R17") (pin "1") (pinfunction "1_1") (pintype "passive"))
      (node (ref "R18") (pin "2") (pinfunction "2_2") (pintype "passive"))
      (node (ref "U$8") (pin "3") (pinfunction "FB_3") (pintype "bidirectional"))
    )
    (net (code "34") (name "Net-(U$8-SW)") (class "Default")
      (node (ref "U$14") (pin "P$2") (pinfunction "P$2_P$2") (pintype "bidirectional"))
      (node (ref "U$8") (pin "1") (pinfunction "SW_1") (pintype "bidirectional"))
      (node (ref "U$9") (pin "ANODE") (pinfunction "ANODE_ANODE") (pintype "bidirectional"))
    )
    (net (code "35") (name "Net-(U$8-{slash}SHDN)") (class "Default")
      (node (ref "R19") (pin "2") (pinfunction "2_2") (pintype "passive"))
      (node (ref "U$8") (pin "4") (pinfunction "/SHDN_4") (pintype "bidirectional"))
    )
    (net (code "36") (name "Net-(U$11-IO1)") (class "Default")
      (node (ref "JP8") (pin "1") (pinfunction "1_1") (pintype "passive"))
      (node (ref "U$11") (pin "P1") (pinfunction "IO1_P1") (pintype "bidirectional"))
      (node (ref "U$4") (pin "1") (pinfunction "P1_1") (pintype "bidirectional"))
      (node (ref "U$4") (pin "4") (pinfunction "P4_4") (pintype "bidirectional"))
    )
    (net (code "37") (name "Net-(U$11-IO2)") (class "Default")
      (node (ref "JP8") (pin "2") (pinfunction "2_2") (pintype "passive"))
      (node (ref "U$11") (pin "P3") (pinfunction "IO2_P3") (pintype "bidirectional"))
      (node (ref "U$6") (pin "1") (pinfunction "P1_1") (pintype "bidirectional"))
      (node (ref "U$6") (pin "4") (pinfunction "P4_4") (pintype "bidirectional"))
    )
    (net (code "38") (name "Net-(U$11-IO3)") (class "Default")
      (node (ref "JP7") (pin "2") (pinfunction "2_2") (pintype "passive"))
      (node (ref "U$11") (pin "P4") (pinfunction "IO3_P4") (pintype "bidirectional"))
      (node (ref "U$5") (pin "1") (pinfunction "P1_1") (pintype "bidirectional"))
      (node (ref "U$5") (pin "4") (pinfunction "P4_4") (pintype "bidirectional"))
    )
    (net (code "39") (name "Net-(U$11-IO4)") (class "Default")
      (node (ref "JP7") (pin "1") (pinfunction "1_1") (pintype "passive"))
      (node (ref "U$11") (pin "P6") (pinfunction "IO4_P6") (pintype "bidirectional"))
      (node (ref "U$2") (pin "1") (pinfunction "P1_1") (pintype "bidirectional"))
      (node (ref "U$2") (pin "4") (pinfunction "P4_4") (pintype "bidirectional"))
    )
    (net (code "40") (name "Net-(U1-IN+)") (class "Default")
      (node (ref "C9") (pin "1") (pinfunction "1_1") (pintype "passive"))
      (node (ref "R16") (pin "1") (pinfunction "1_1") (pintype "passive"))
      (node (ref "R25") (pin "2") (pinfunction "2_2") (pintype "passive"))
      (node (ref "U1") (pin "3") (pinfunction "IN+_3") (pintype "bidirectional"))
    )
    (net (code "41") (name "Net-(U1-IN-)") (class "Default")
      (node (ref "C8") (pin "2") (pinfunction "2_2") (pintype "passive"))
      (node (ref "R14") (pin "1") (pinfunction "1_1") (pintype "passive"))
      (node (ref "U1") (pin "4") (pinfunction "IN-_4") (pintype "bidirectional"))
    )
    (net (code "42") (name "Net-(U1-OUT)") (class "Default")
      (node (ref "C8") (pin "1") (pinfunction "1_1") (pintype "passive"))
      (node (ref "R15") (pin "1") (pinfunction "1_1") (pintype "passive"))
      (node (ref "U1") (pin "1") (pinfunction "OUT_1") (pintype "bidirectional"))
    )
    (net (code "43") (name "SCK") (class "Default")
      (node (ref "JP1") (pin "5") (pinfunction "5_5") (pintype "passive"))
      (node (ref "U$1") (pin "P15") (pinfunction "PA5_P15") (pintype "bidirectional"))
    )
    (net (code "44") (name "SCL") (class "Default")
      (node (ref "JP1") (pin "4") (pinfunction "4_4") (pintype "passive"))
      (node (ref "U$1") (pin "P6") (pinfunction "PF1_P6") (pintype "bidirectional"))
    )
    (net (code "45") (name "SDA") (class "Default")
      (node (ref "JP1") (pin "6") (pinfunction "6_6") (pintype "passive"))
      (node (ref "U$1") (pin "P5") (pinfunction "PF0_P5") (pintype "bidirectional"))
    )
    (net (code "46") (name "SPI_CS") (class "Default")
      (node (ref "JP1") (pin "3") (pinfunction "3_3") (pintype "passive"))
      (node (ref "U$1") (pin "P18") (pinfunction "PB0_P18") (pintype "bidirectional"))
    )
    (net (code "47") (name "SWCLK") (class "Default")
      (node (ref "JP2") (pin "2") (pinfunction "2_2") (pintype "passive"))
      (node (ref "U$1") (pin "P37") (pinfunction "PA14_P37") (pintype "bidirectional"))
    )
    (net (code "48") (name "SWDIO") (class "Default")
      (node (ref "JP2") (pin "3") (pinfunction "3_3") (pintype "passive"))
      (node (ref "U$1") (pin "P34") (pinfunction "PA13_P34") (pintype "bidirectional"))
    )
    (net (code "49") (name "USB_DM") (class "Default")
      (node (ref "U$1") (pin "P32") (pinfunction "PA11_P32") (pintype "bidirectional"))
      (node (ref "U$12") (pin "P1") (pinfunction "IO1_P1") (pintype "bidirectional"))
      (node (ref "U$3") (pin "P2") (pinfunction "DM_P2") (pintype "bidirectional"))
    )
    (net (code "50") (name "USB_DP") (class "Default")
      (node (ref "U$1") (pin "P33") (pinfunction "PA12_P33") (pintype "bidirectional"))
      (node (ref "U$12") (pin "P3") (pinfunction "IO2_P3") (pintype "bidirectional"))
      (node (ref "U$3") (pin "P3") (pinfunction "DP_P3") (pintype "bidirectional"))
    )
    (net (code "51") (name "VUSB") (class "Default")
      (node (ref "C16") (pin "1") (pinfunction "1_1") (pintype "passive"))
      (node (ref "C22") (pin "1") (pinfunction "1_1") (pintype "passive"))
      (node (ref "C23") (pin "1") (pinfunction "1_1") (pintype "passive"))
      (node (ref "C24") (pin "1") (pinfunction "1_1") (pintype "passive"))
      (node (ref "C25") (pin "1") (pinfunction "1_1") (pintype "passive"))
      (node (ref "D2") (pin "2") (pinfunction "2_2") (pintype "bidirectional"))
      (node (ref "R19") (pin "1") (pinfunction "1_1") (pintype "passive"))
      (node (ref "U$10") (pin "CATHODE") (pinfunction "CATHODE_CATHODE") (pintype "bidirectional"))
      (node (ref "U$11") (pin "P5") (pinfunction "VCC_P5") (pintype "power_in"))
      (node (ref "U$12") (pin "P5") (pinfunction "VCC_P5") (pintype "power_in"))
      (node (ref "U$13") (pin "CATHODE") (pinfunction "CATHODE_CATHODE") (pintype "bidirectional"))
      (node (ref "U$14") (pin "P$1") (pinfunction "P$1_P$1") (pintype "bidirectional"))
      (node (ref "U$2") (pin "2") (pinfunction "P2_2") (pintype "power_in"))
      (node (ref "U$4") (pin "2") (pinfunction "P2_2") (pintype "power_in"))
      (node (ref "U$5") (pin "2") (pinfunction "P2_2") (pintype "power_in"))
      (node (ref "U$6") (pin "2") (pinfunction "P2_2") (pintype "power_in"))
      (node (ref "U$7") (pin "P$1") (pinfunction "P$1_P$1") (pintype "bidirectional"))
      (node (ref "U$8") (pin "5") (pinfunction "VIN_5") (pintype "bidirectional"))
    )
    (net (code "52") (name "XBARDUAL_OUT") (class "Default")
      (node (ref "C6") (pin "1") (pinfunction "1_1") (pintype "passive"))
      (node (ref "R10") (pin "2") (pinfunction "2_2") (pintype "passive"))
      (node (ref "R9") (pin "2") (pinfunction "2_2") (pintype "passive"))
      (node (ref "U$5") (pin "3") (pinfunction "P3_3") (pintype "bidirectional"))
    )
    (net (code "53") (name "XCOARSE_IN") (class "Default")
      (node (ref "IC3") (pin "5") (pinfunction "I_5") (pintype "input"))
      (node (ref "R5") (pin "1") (pinfunction "1_1") (pintype "passive"))
      (node (ref "U$1") (pin "P38") (pinfunction "PA15_P38") (pintype "bidirectional"))
    )
    (net (code "54") (name "XDUAL_OUT") (class "Default")
      (node (ref "C4") (pin "1") (pinfunction "1_1") (pintype "passive"))
      (node (ref "R5") (pin "2") (pinfunction "2_2") (pintype "passive"))
      (node (ref "R6") (pin "2") (pinfunction "2_2") (pintype "passive"))
      (node (ref "U$2") (pin "3") (pinfunction "P3_3") (pintype "bidirectional"))
    )
    (net (code "55") (name "XFINE_IN") (class "Default")
      (node (ref "IC3") (pin "9") (pinfunction "I_9") (pintype "input"))
      (node (ref "R6") (pin "1") (pinfunction "1_1") (pintype "passive"))
      (node (ref "U$1") (pin "P39") (pinfunction "PB3_P39") (pintype "bidirectional"))
    )
    (net (code "56") (name "YBARDUAL_OUT") (class "Default")
      (node (ref "C7") (pin "1") (pinfunction "1_1") (pintype "passive"))
      (node (ref "R11") (pin "2") (pinfunction "2_2") (pintype "passive"))
      (node (ref "R12") (pin "2") (pinfunction "2_2") (pintype "passive"))
      (node (ref "U$6") (pin "3") (pinfunction "P3_3") (pintype "bidirectional"))
    )
    (net (code "57") (name "YCOARSE_IN") (class "Default")
      (node (ref "IC3") (pin "11") (pinfunction "I_11") (pintype "input"))
      (node (ref "R7") (pin "1") (pinfunction "1_1") (pintype "passive"))
      (node (ref "U$1") (pin "P21") (pinfunction "PB10_P21") (pintype "bidirectional"))
    )
    (net (code "58") (name "YDUAL_OUT") (class "Default")
      (node (ref "C5") (pin "1") (pinfunction "1_1") (pintype "passive"))
      (node (ref "R7") (pin "2") (pinfunction "2_2") (pintype "passive"))
      (node (ref "R8") (pin "2") (pinfunction "2_2") (pintype "passive"))
      (node (ref "U$4") (pin "3") (pinfunction "P3_3") (pintype "bidirectional"))
    )
    (net (code "59") (name "YFINE_IN") (class "Default")
      (node (ref "IC3") (pin "13") (pinfunction "I_13") (pintype "input"))
      (node (ref "R8") (pin "1") (pinfunction "1_1") (pintype "passive"))
      (node (ref "U$1") (pin "P22") (pinfunction "PB11_P22") (pintype "bidirectional"))
    )
    (net (code "60") (name "unconnected-(IC3A-O-Pad2)") (class "Default")
      (node (ref "IC3") (pin "2") (pinfunction "O_2") (pintype "output"))
    )
    (net (code "61") (name "unconnected-(IC3B-O-Pad4)") (class "Default")
      (node (ref "IC3") (pin "4") (pinfunction "O_4") (pintype "output"))
    )
    (net (code "62") (name "unconnected-(U$1-PA4-PadP14)") (class "Default")
      (node (ref "U$1") (pin "P14") (pinfunction "PA4_P14") (pintype "bidirectional"))
    )
    (net (code "63") (name "unconnected-(U$1-PA8-PadP29)") (class "Default")
      (node (ref "U$1") (pin "P29") (pinfunction "PA8_P29") (pintype "bidirectional"))
    )
    (net (code "64") (name "unconnected-(U$1-PA9-PadP30)") (class "Default")
      (node (ref "U$1") (pin "P30") (pinfunction "PA9_P30") (pintype "bidirectional"))
    )
    (net (code "65") (name "unconnected-(U$1-PA10-PadP31)") (class "Default")
      (node (ref "U$1") (pin "P31") (pinfunction "PA10_P31") (pintype "bidirectional"))
    )
    (net (code "66") (name "unconnected-(U$1-PB1-PadP19)") (class "Default")
      (node (ref "U$1") (pin "P19") (pinfunction "PB1_P19") (pintype "bidirectional"))
    )
    (net (code "67") (name "unconnected-(U$1-PB2-PadP20)") (class "Default")
      (node (ref "U$1") (pin "P20") (pinfunction "PB2_P20") (pintype "bidirectional"))
    )
    (net (code "68") (name "unconnected-(U$1-PB5-PadP41)") (class "Default")
      (node (ref "U$1") (pin "P41") (pinfunction "PB5_P41") (pintype "bidirectional"))
    )
    (net (code "69") (name "unconnected-(U$1-PB6-PadP42)") (class "Default")
      (node (ref "U$1") (pin "P42") (pinfunction "PB6_P42") (pintype "bidirectional"))
    )
    (net (code "70") (name "unconnected-(U$1-PB7-PadP43)") (class "Default")
      (node (ref "U$1") (pin "P43") (pinfunction "PB7_P43") (pintype "bidirectional"))
    )
    (net (code "71") (name "unconnected-(U$1-PB8-PadP45)") (class "Default")
      (node (ref "U$1") (pin "P45") (pinfunction "PB8_P45") (pintype "bidirectional"))
    )
    (net (code "72") (name "unconnected-(U$1-PB9-PadP46)") (class "Default")
      (node (ref "U$1") (pin "P46") (pinfunction "PB9_P46") (pintype "bidirectional"))
    )
    (net (code "73") (name "unconnected-(U$1-PC13-PadP2)") (class "Default")
      (node (ref "U$1") (pin "P2") (pinfunction "PC13_P2") (pintype "bidirectional"))
    )
    (net (code "74") (name "unconnected-(U$1-PC14-PadP3)") (class "Default")
      (node (ref "U$1") (pin "P3") (pinfunction "PC14_P3") (pintype "bidirectional"))
    )
    (net (code "75") (name "unconnected-(U$1-PC15-PadP4)") (class "Default")
      (node (ref "U$1") (pin "P4") (pinfunction "PC15_P4") (pintype "bidirectional"))
    )
    (net (code "76") (name "unconnected-(U$12-IO3-PadP4)") (class "Default")
      (node (ref "U$12") (pin "P4") (pinfunction "IO3_P4") (pintype "bidirectional"))
    )
    (net (code "77") (name "unconnected-(U$12-IO4-PadP6)") (class "Default")
      (node (ref "U$12") (pin "P6") (pinfunction "IO4_P6") (pintype "bidirectional"))
    )
  )
)
